# Relay_Schem_NO.net
KiCad netlist of a schematic drawn in Altium Designer
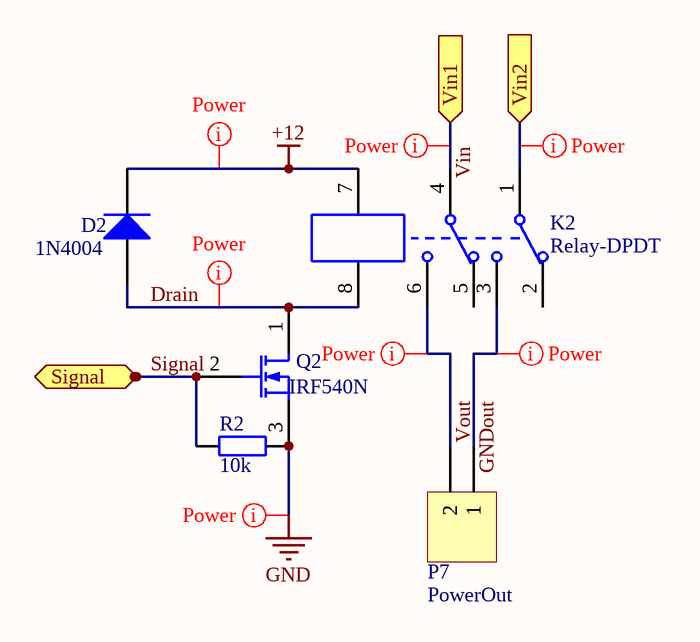
[diagram p0: Relay_Schem_NO.SchDoc]

(export (version "E")
  (design (tool "Eeschema 10.0.6"))
  (components
    (comp (ref "D2")
      (value "1N4004")
      (footprint "DIODE-0.3-SI")
      (description "1 Amp General Purpose Rectifier")
      (fields (field (name "PUBLISHER") "Altium Limited"))
      (libsource (lib "Miscellaneous Devices") (part "Diode 1N4005"))
    )
    (comp (ref "K2")
      (value "Relay-DPDT")
      (footprint "Relay_95.12 Socket - With Screw")
      (description "Dual-Pole Dual-Throw Relay")
      (fields (field (name "PUBLISHER") "Altium Limited"))
      (libsource (lib "Miscellaneous Devices") (part "Relay-DPDT"))
    )
    (comp (ref "P7")
      (value "PowerOut")
      (footprint "CONN-WAFER-2x1")
      (description "Header, 2-Pin")
      (fields (field (name "PUBLISHER") "Altium Limited"))
      (libsource (lib "Miscellaneous Connectors") (part "Header 2"))
    )
    (comp (ref "Q2")
      (value "IRF540N")
      (footprint "TO-220")
      (description "N-Channel MOSFET")
      (fields (field (name "PUBLISHER") "Altium Limited"))
      (libsource (lib "Miscellaneous Devices") (part "MOSFET-N"))
    )
    (comp (ref "R2")
      (value "10k")
      (footprint "RES-0.4")
      (description "Resistor")
      (fields (field (name "PUBLISHER") "Altium Limited"))
      (libsource (lib "Miscellaneous Devices") (part "Res2"))
    )
  )
  (nets
    (net (code "1") (name "+12") (class "Default")
      (node (ref "D2") (pin "2") (pinfunction "K_2") (pintype "passive"))
      (node (ref "K2") (pin "7") (pinfunction "7_7") (pintype "passive"))
    )
    (net (code "2") (name "/Drain") (class "Default")
      (node (ref "D2") (pin "1") (pinfunction "A_1") (pintype "passive"))
      (node (ref "K2") (pin "8") (pinfunction "8_8") (pintype "passive"))
      (node (ref "Q2") (pin "1") (pinfunction "D_1") (pintype "passive"))
    )
    (net (code "3") (name "/GNDout") (class "Default")
      (node (ref "K2") (pin "3") (pinfunction "3_3") (pintype "passive"))
      (node (ref "P7") (pin "1") (pinfunction "1_1") (pintype "passive"))
    )
    (net (code "4") (name "/Signal") (class "Default")
      (node (ref "Q2") (pin "2") (pinfunction "G_2") (pintype "passive"))
      (node (ref "R2") (pin "1") (pinfunction "1_1") (pintype "passive"))
    )
    (net (code "5") (name "/Vin") (class "Default")
      (node (ref "K2") (pin "4") (pinfunction "4_4") (pintype "passive"))
    )
    (net (code "6") (name "/Vin2") (class "Default")
      (node (ref "K2") (pin "1") (pinfunction "1_1") (pintype "passive"))
    )
    (net (code "7") (name "/Vout") (class "Default")
      (node (ref "K2") (pin "6") (pinfunction "6_6") (pintype "passive"))
      (node (ref "P7") (pin "2") (pinfunction "2_2") (pintype "passive"))
    )
    (net (code "8") (name "GND") (class "Default")
      (node (ref "Q2") (pin "3") (pinfunction "S_3") (pintype "passive"))
      (node (ref "R2") (pin "2") (pinfunction "2_2") (pintype "passive"))
    )
    (net (code "9") (name "unconnected-(K2-Pad2)") (class "Default")
      (node (ref "K2") (pin "2") (pinfunction "2_2") (pintype "passive"))
    )
    (net (code "10") (name "unconnected-(K2-Pad5)") (class "Default")
      (node (ref "K2") (pin "5") (pinfunction "5_5") (pintype "passive"))
    )
  )
)
